# boost.net
KiCad netlist of a schematic drawn in EAGLE
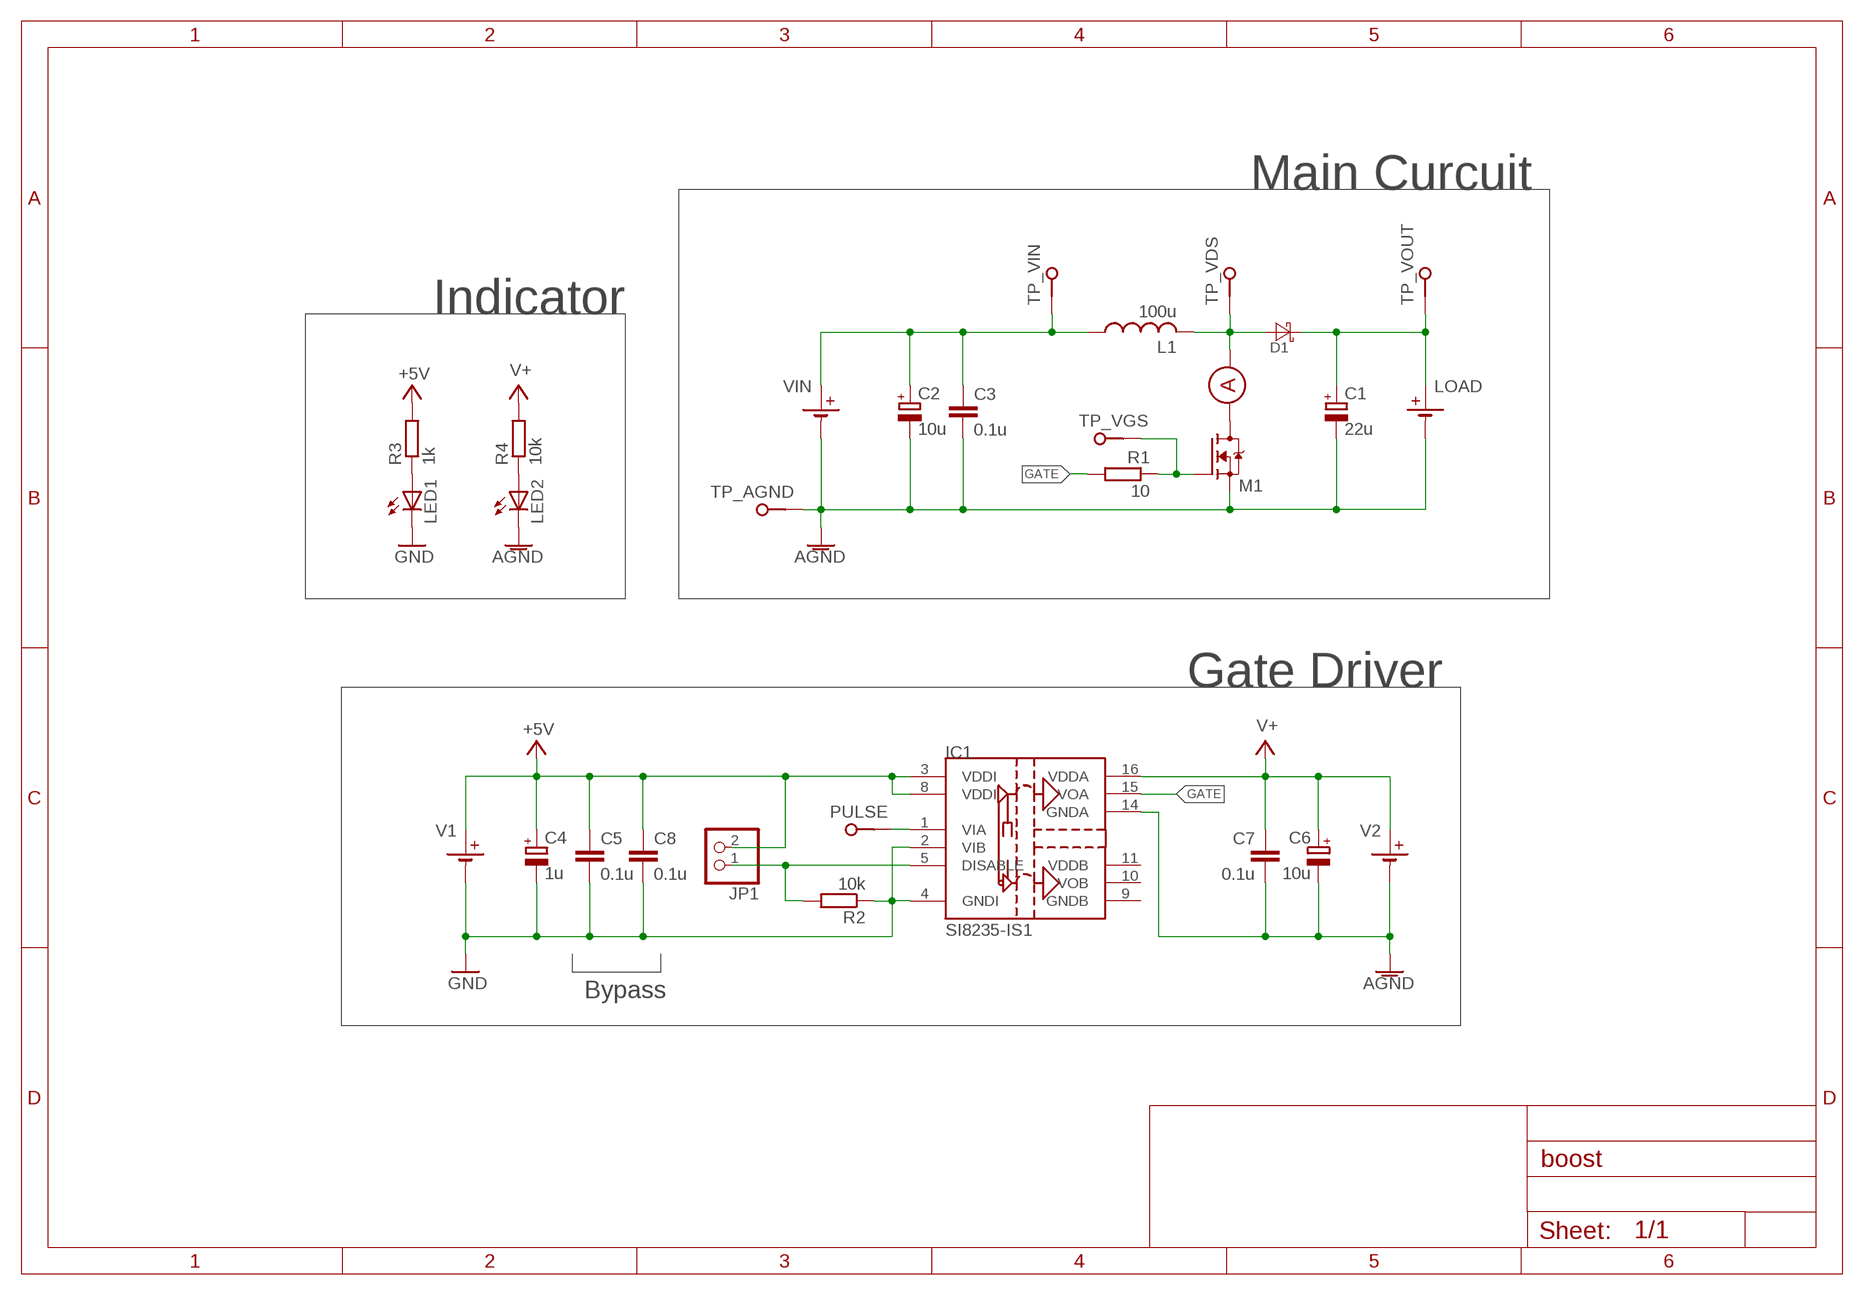
[diagram p0: schematic, sheet 1]

(export (version "E")
  (design (tool "Eeschema 10.0.6"))
  (components
    (comp (ref "C1")
      (value "22u")
      (footprint "eagle-import:E5-10,5")
      (libsource (lib "eagle-import") (part "resistor_CPOL-EUE5-10.5"))
    )
    (comp (ref "C2")
      (value "10u")
      (footprint "eagle-import:E2,5-6")
      (libsource (lib "eagle-import") (part "resistor_CPOL-EUE2.5-6"))
    )
    (comp (ref "C3")
      (value "0.1u")
      (footprint "eagle-import:C0805")
      (libsource (lib "eagle-import") (part "C-EUC0805"))
    )
    (comp (ref "C4")
      (value "1u")
      (footprint "eagle-import:E2-5")
      (libsource (lib "eagle-import") (part "CPOL-EUE2-5"))
    )
    (comp (ref "C5")
      (value "0.1u")
      (footprint "eagle-import:C0805")
      (libsource (lib "eagle-import") (part "C-EUC0805"))
    )
    (comp (ref "C6")
      (value "10u")
      (footprint "eagle-import:E2,5-6")
      (libsource (lib "eagle-import") (part "resistor_CPOL-EUE2.5-6"))
    )
    (comp (ref "C7")
      (value "0.1u")
      (footprint "eagle-import:C0805")
      (libsource (lib "eagle-import") (part "C-EUC0805"))
    )
    (comp (ref "C8")
      (value "0.1u")
      (footprint "eagle-import:C0805")
      (libsource (lib "eagle-import") (part "C-EUC0805"))
    )
    (comp (ref "D1")
      (value "RB088LAM150TFTR")
      (footprint "eagle-import:SOD128")
      (libsource (lib "eagle-import") (part "RB088LAM150TFTR"))
    )
    (comp (ref "IC1")
      (value "SI8235-IS1")
      (footprint "eagle-import:SO16")
      (libsource (lib "eagle-import") (part "SI8235-IS1"))
    )
    (comp (ref "JP1")
      (value "PINHD-1X2")
      (footprint "eagle-import:1X02")
      (libsource (lib "eagle-import") (part "PINHD-1X2"))
    )
    (comp (ref "L1")
      (value "100u")
      (footprint "eagle-import:MURATA_19RXXXC")
      (libsource (lib "eagle-import") (part "L_MURATA"))
    )
    (comp (ref "LED1")
      (value "LEDCHIPLED_0805")
      (footprint "eagle-import:CHIPLED_0805")
      (libsource (lib "eagle-import") (part "LEDCHIPLED_0805"))
    )
    (comp (ref "LED2")
      (value "LEDCHIPLED_0805")
      (footprint "eagle-import:CHIPLED_0805")
      (libsource (lib "eagle-import") (part "LEDCHIPLED_0805"))
    )
    (comp (ref "LOAD")
      (value "POWER_SUPPLY_L")
      (footprint "eagle-import:SOURCE_HIGH")
      (libsource (lib "eagle-import") (part "POWER_SUPPLY_L"))
    )
    (comp (ref "M1")
      (value "FET_ON_SOCKET")
      (footprint "eagle-import:ICTS-TO3P")
      (libsource (lib "eagle-import") (part "FET_ON_SOCKET"))
    )
    (comp (ref "PULSE")
      (value "PIN")
      (footprint "eagle-import:PIN")
      (libsource (lib "eagle-import") (part "PIN"))
    )
    (comp (ref "R1")
      (value "10")
      (footprint "eagle-import:R2512")
      (libsource (lib "eagle-import") (part "R-EU_R2512"))
    )
    (comp (ref "R2")
      (value "10k")
      (footprint "eagle-import:R0805")
      (libsource (lib "eagle-import") (part "R-EU_R0805"))
    )
    (comp (ref "R3")
      (value "1k")
      (footprint "eagle-import:R0805")
      (libsource (lib "eagle-import") (part "R-EU_R0805"))
    )
    (comp (ref "R4")
      (value "10k")
      (footprint "eagle-import:R0805")
      (libsource (lib "eagle-import") (part "R-EU_R0805"))
    )
    (comp (ref "TP_AGND")
      (value "PIN")
      (footprint "eagle-import:PIN")
      (libsource (lib "eagle-import") (part "PIN"))
    )
    (comp (ref "TP_VDS")
      (value "PIN")
      (footprint "eagle-import:PIN")
      (libsource (lib "eagle-import") (part "PIN"))
    )
    (comp (ref "TP_VGS")
      (value "PIN")
      (footprint "eagle-import:PIN")
      (libsource (lib "eagle-import") (part "PIN"))
    )
    (comp (ref "TP_VIN")
      (value "PIN")
      (footprint "eagle-import:PIN")
      (libsource (lib "eagle-import") (part "PIN"))
    )
    (comp (ref "TP_VOUT")
      (value "PIN")
      (footprint "eagle-import:PIN")
      (libsource (lib "eagle-import") (part "PIN"))
    )
    (comp (ref "U$1")
      (value "AMMETER")
      (footprint "eagle-import:AMMETER")
      (libsource (lib "eagle-import") (part "AMMETER"))
    )
    (comp (ref "V1")
      (value "POWER_SUPPLY")
      (footprint "eagle-import:526702AX")
      (libsource (lib "eagle-import") (part "POWER_SUPPLY"))
    )
    (comp (ref "V2")
      (value "POWER_SUPPLY")
      (footprint "eagle-import:526702AX")
      (libsource (lib "eagle-import") (part "POWER_SUPPLY"))
    )
    (comp (ref "VIN")
      (value "POWER_SUPPLY_L")
      (footprint "eagle-import:SOURCE_HIGH")
      (libsource (lib "eagle-import") (part "POWER_SUPPLY_L"))
    )
  )
  (nets
    (net (code "1") (name "+5V") (class "Default")
      (node (ref "C4") (pin "+") (pinfunction "+_+") (pintype "passive"))
      (node (ref "C5") (pin "1") (pinfunction "1_1") (pintype "passive"))
      (node (ref "C8") (pin "1") (pinfunction "1_1") (pintype "passive"))
      (node (ref "IC1") (pin "3") (pinfunction "VDDI_3") (pintype "power_in"))
      (node (ref "IC1") (pin "8") (pinfunction "VDDI_8") (pintype "power_in"))
      (node (ref "JP1") (pin "2") (pinfunction "2_2") (pintype "passive"))
      (node (ref "R3") (pin "2") (pinfunction "2_2") (pintype "passive"))
      (node (ref "V1") (pin "P") (pinfunction "P_P") (pintype "passive"))
    )
    (net (code "2") (name "/GNDB") (class "Default")
      (node (ref "IC1") (pin "9") (pinfunction "GNDB_9") (pintype "power_in"))
    )
    (net (code "3") (name "/VDDB") (class "Default")
      (node (ref "IC1") (pin "11") (pinfunction "VDDB_11") (pintype "power_in"))
    )
    (net (code "4") (name "AGND") (class "Default")
      (node (ref "C1") (pin "-") (pinfunction "-_-") (pintype "passive"))
      (node (ref "C2") (pin "-") (pinfunction "-_-") (pintype "passive"))
      (node (ref "C3") (pin "2") (pinfunction "2_2") (pintype "passive"))
      (node (ref "C6") (pin "-") (pinfunction "-_-") (pintype "passive"))
      (node (ref "C7") (pin "2") (pinfunction "2_2") (pintype "passive"))
      (node (ref "IC1") (pin "14") (pinfunction "GNDA_14") (pintype "power_in"))
      (node (ref "LED2") (pin "C") (pinfunction "C_C") (pintype "passive"))
      (node (ref "LOAD") (pin "N") (pinfunction "N_N") (pintype "passive"))
      (node (ref "M1") (pin "S0") (pinfunction "S_S0") (pintype "passive"))
      (node (ref "M1") (pin "S1") (pinfunction "S_S1") (pintype "passive"))
      (node (ref "TP_AGND") (pin "1") (pinfunction "KL_1") (pintype "passive"))
      (node (ref "V2") (pin "N") (pinfunction "N_N") (pintype "passive"))
      (node (ref "VIN") (pin "N") (pinfunction "N_N") (pintype "passive"))
    )
    (net (code "5") (name "GATE") (class "Default")
      (node (ref "IC1") (pin "15") (pinfunction "VOA_15") (pintype "output"))
      (node (ref "R1") (pin "2") (pinfunction "2_2") (pintype "passive"))
    )
    (net (code "6") (name "GND") (class "Default")
      (node (ref "C4") (pin "-") (pinfunction "-_-") (pintype "passive"))
      (node (ref "C5") (pin "2") (pinfunction "2_2") (pintype "passive"))
      (node (ref "C8") (pin "2") (pinfunction "2_2") (pintype "passive"))
      (node (ref "IC1") (pin "2") (pinfunction "VIB_2") (pintype "input"))
      (node (ref "IC1") (pin "4") (pinfunction "GNDI_4") (pintype "power_in"))
      (node (ref "LED1") (pin "C") (pinfunction "C_C") (pintype "passive"))
      (node (ref "R2") (pin "1") (pinfunction "1_1") (pintype "passive"))
      (node (ref "V1") (pin "N") (pinfunction "N_N") (pintype "passive"))
    )
    (net (code "7") (name "Net-(IC1-DISABLE)") (class "Default")
      (node (ref "IC1") (pin "5") (pinfunction "DISABLE_5") (pintype "input"))
      (node (ref "JP1") (pin "1") (pinfunction "1_1") (pintype "passive"))
      (node (ref "R2") (pin "2") (pinfunction "2_2") (pintype "passive"))
    )
    (net (code "8") (name "Net-(IC1-VIA)") (class "Default")
      (node (ref "IC1") (pin "1") (pinfunction "VIA_1") (pintype "input"))
      (node (ref "PULSE") (pin "1") (pinfunction "KL_1") (pintype "passive"))
    )
    (net (code "9") (name "Net-(LED1-PadA)") (class "Default")
      (node (ref "LED1") (pin "A") (pinfunction "A_A") (pintype "passive"))
      (node (ref "R3") (pin "1") (pinfunction "1_1") (pintype "passive"))
    )
    (net (code "10") (name "Net-(LED2-PadA)") (class "Default")
      (node (ref "LED2") (pin "A") (pinfunction "A_A") (pintype "passive"))
      (node (ref "R4") (pin "1") (pinfunction "1_1") (pintype "passive"))
    )
    (net (code "11") (name "Net-(M1-D-PadD0)") (class "Default")
      (node (ref "M1") (pin "D0") (pinfunction "D_D0") (pintype "passive"))
      (node (ref "M1") (pin "D1") (pinfunction "D_D1") (pintype "passive"))
      (node (ref "U$1") (pin "P$1") (pinfunction "P$1_P$1") (pintype "bidirectional"))
    )
    (net (code "12") (name "Net-(TP_VDS-KL)") (class "Default")
      (node (ref "D1") (pin "A") (pinfunction "A_A") (pintype "passive"))
      (node (ref "L1") (pin "2") (pinfunction "2_2") (pintype "passive"))
      (node (ref "TP_VDS") (pin "1") (pinfunction "KL_1") (pintype "passive"))
      (node (ref "U$1") (pin "P$2") (pinfunction "P$2_P$2") (pintype "bidirectional"))
    )
    (net (code "13") (name "Net-(TP_VGS-KL)") (class "Default")
      (node (ref "M1") (pin "G0") (pinfunction "G_G0") (pintype "passive"))
      (node (ref "M1") (pin "G1") (pinfunction "G_G1") (pintype "passive"))
      (node (ref "R1") (pin "1") (pinfunction "1_1") (pintype "passive"))
      (node (ref "TP_VGS") (pin "1") (pinfunction "KL_1") (pintype "passive"))
    )
    (net (code "14") (name "Net-(TP_VIN-KL)") (class "Default")
      (node (ref "C2") (pin "+") (pinfunction "+_+") (pintype "passive"))
      (node (ref "C3") (pin "1") (pinfunction "1_1") (pintype "passive"))
      (node (ref "L1") (pin "1") (pinfunction "1_1") (pintype "passive"))
      (node (ref "TP_VIN") (pin "1") (pinfunction "KL_1") (pintype "passive"))
      (node (ref "VIN") (pin "P") (pinfunction "P_P") (pintype "passive"))
    )
    (net (code "15") (name "Net-(TP_VOUT-KL)") (class "Default")
      (node (ref "C1") (pin "+") (pinfunction "+_+") (pintype "passive"))
      (node (ref "D1") (pin "C") (pinfunction "C_C") (pintype "passive"))
      (node (ref "LOAD") (pin "P") (pinfunction "P_P") (pintype "passive"))
      (node (ref "TP_VOUT") (pin "1") (pinfunction "KL_1") (pintype "passive"))
    )
    (net (code "16") (name "V+") (class "Default")
      (node (ref "C6") (pin "+") (pinfunction "+_+") (pintype "passive"))
      (node (ref "C7") (pin "1") (pinfunction "1_1") (pintype "passive"))
      (node (ref "IC1") (pin "16") (pinfunction "VDDA_16") (pintype "power_in"))
      (node (ref "R4") (pin "2") (pinfunction "2_2") (pintype "passive"))
      (node (ref "V2") (pin "P") (pinfunction "P_P") (pintype "passive"))
    )
    (net (code "17") (name "unconnected-(IC1-VOB-Pad10)") (class "Default")
      (node (ref "IC1") (pin "10") (pinfunction "VOB_10") (pintype "output"))
    )
  )
)
